# spider_mx8.net
KiCad netlist of a schematic drawn in EAGLE
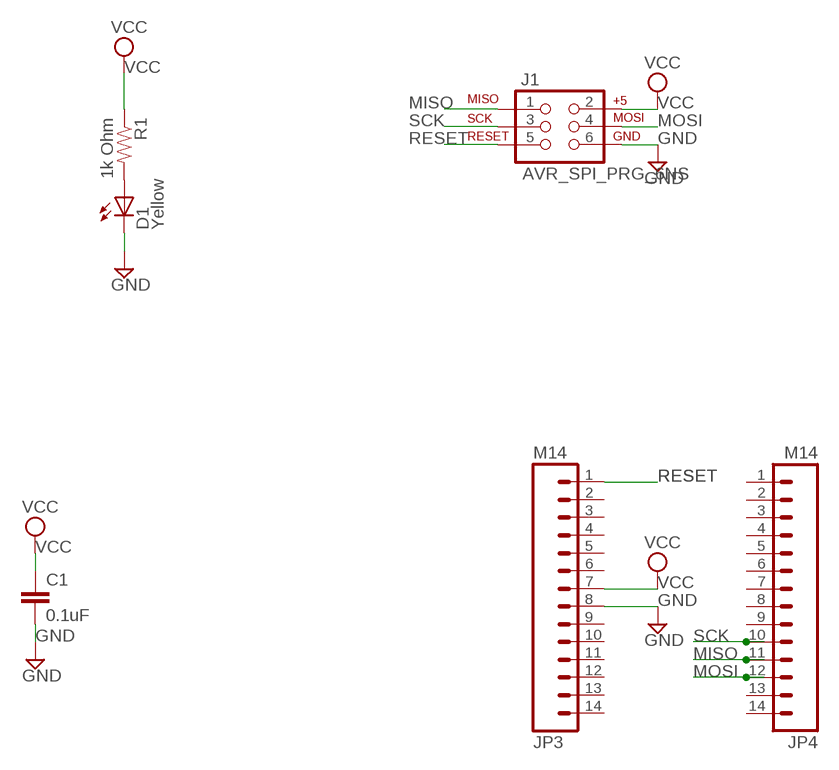
[diagram p0: schematic, sheet 1]

(export (version "E")
  (design (tool "Eeschema 10.0.6"))
  (components
    (comp (ref "C1")
      (value "0.1uF")
      (footprint "eagle-import:1206")
      (libsource (lib "eagle-import") (part "CAP1206"))
    )
    (comp (ref "D1")
      (value "Yellow")
      (footprint "eagle-import:LED-1206")
      (libsource (lib "eagle-import") (part "LED-YELLOWLILYPAD"))
    )
    (comp (ref "J1")
      (value "AVR_SPI_PRG_6NS")
      (footprint "eagle-import:2X3-NS")
      (libsource (lib "eagle-import") (part "AVR_SPI_PRG_6NS"))
    )
    (comp (ref "JP3")
      (value "M14")
      (footprint "eagle-import:1X14")
      (libsource (lib "eagle-import") (part "M14"))
    )
    (comp (ref "JP4")
      (value "M14")
      (footprint "eagle-import:1X14")
      (libsource (lib "eagle-import") (part "M14"))
    )
    (comp (ref "R1")
      (value "1k Ohm")
      (footprint "eagle-import:1206")
      (libsource (lib "eagle-import") (part "RESISTOR1206"))
    )
  )
  (nets
    (net (code "1") (name "/MISO") (class "Default")
      (node (ref "J1") (pin "1") (pinfunction "1_1") (pintype "passive"))
      (node (ref "JP4") (pin "11") (pinfunction "11_11") (pintype "passive"))
    )
    (net (code "2") (name "/MOSI") (class "Default")
      (node (ref "J1") (pin "4") (pinfunction "4_4") (pintype "passive"))
      (node (ref "JP4") (pin "12") (pinfunction "12_12") (pintype "passive"))
    )
    (net (code "3") (name "/RESET") (class "Default")
      (node (ref "J1") (pin "5") (pinfunction "5_5") (pintype "passive"))
      (node (ref "JP3") (pin "1") (pinfunction "1_1") (pintype "passive"))
    )
    (net (code "4") (name "/SCK") (class "Default")
      (node (ref "J1") (pin "3") (pinfunction "3_3") (pintype "passive"))
      (node (ref "JP4") (pin "10") (pinfunction "10_10") (pintype "passive"))
    )
    (net (code "5") (name "GND") (class "Default")
      (node (ref "C1") (pin "2") (pinfunction "2_2") (pintype "passive"))
      (node (ref "D1") (pin "C") (pinfunction "C_C") (pintype "passive"))
      (node (ref "J1") (pin "6") (pinfunction "6_6") (pintype "passive"))
      (node (ref "JP3") (pin "8") (pinfunction "8_8") (pintype "passive"))
    )
    (net (code "6") (name "Net-(D1-PadA)") (class "Default")
      (node (ref "D1") (pin "A") (pinfunction "A_A") (pintype "passive"))
      (node (ref "R1") (pin "2") (pinfunction "2_2") (pintype "passive"))
    )
    (net (code "7") (name "VCC") (class "Default")
      (node (ref "C1") (pin "1") (pinfunction "1_1") (pintype "passive"))
      (node (ref "J1") (pin "2") (pinfunction "2_2") (pintype "passive"))
      (node (ref "JP3") (pin "7") (pinfunction "7_7") (pintype "passive"))
      (node (ref "R1") (pin "1") (pinfunction "1_1") (pintype "passive"))
    )
    (net (code "8") (name "unconnected-(JP3-Pad2)") (class "Default")
      (node (ref "JP3") (pin "2") (pinfunction "2_2") (pintype "passive"))
    )
    (net (code "9") (name "unconnected-(JP3-Pad3)") (class "Default")
      (node (ref "JP3") (pin "3") (pinfunction "3_3") (pintype "passive"))
    )
    (net (code "10") (name "unconnected-(JP3-Pad4)") (class "Default")
      (node (ref "JP3") (pin "4") (pinfunction "4_4") (pintype "passive"))
    )
    (net (code "11") (name "unconnected-(JP3-Pad5)") (class "Default")
      (node (ref "JP3") (pin "5") (pinfunction "5_5") (pintype "passive"))
    )
    (net (code "12") (name "unconnected-(JP3-Pad6)") (class "Default")
      (node (ref "JP3") (pin "6") (pinfunction "6_6") (pintype "passive"))
    )
    (net (code "13") (name "unconnected-(JP3-Pad9)") (class "Default")
      (node (ref "JP3") (pin "9") (pinfunction "9_9") (pintype "passive"))
    )
    (net (code "14") (name "unconnected-(JP3-Pad10)") (class "Default")
      (node (ref "JP3") (pin "10") (pinfunction "10_10") (pintype "passive"))
    )
    (net (code "15") (name "unconnected-(JP3-Pad11)") (class "Default")
      (node (ref "JP3") (pin "11") (pinfunction "11_11") (pintype "passive"))
    )
    (net (code "16") (name "unconnected-(JP3-Pad12)") (class "Default")
      (node (ref "JP3") (pin "12") (pinfunction "12_12") (pintype "passive"))
    )
    (net (code "17") (name "unconnected-(JP3-Pad13)") (class "Default")
      (node (ref "JP3") (pin "13") (pinfunction "13_13") (pintype "passive"))
    )
    (net (code "18") (name "unconnected-(JP3-Pad14)") (class "Default")
      (node (ref "JP3") (pin "14") (pinfunction "14_14") (pintype "passive"))
    )
    (net (code "19") (name "unconnected-(JP4-Pad1)") (class "Default")
      (node (ref "JP4") (pin "1") (pinfunction "1_1") (pintype "passive"))
    )
    (net (code "20") (name "unconnected-(JP4-Pad2)") (class "Default")
      (node (ref "JP4") (pin "2") (pinfunction "2_2") (pintype "passive"))
    )
    (net (code "21") (name "unconnected-(JP4-Pad3)") (class "Default")
      (node (ref "JP4") (pin "3") (pinfunction "3_3") (pintype "passive"))
    )
    (net (code "22") (name "unconnected-(JP4-Pad4)") (class "Default")
      (node (ref "JP4") (pin "4") (pinfunction "4_4") (pintype "passive"))
    )
    (net (code "23") (name "unconnected-(JP4-Pad5)") (class "Default")
      (node (ref "JP4") (pin "5") (pinfunction "5_5") (pintype "passive"))
    )
    (net (code "24") (name "unconnected-(JP4-Pad6)") (class "Default")
      (node (ref "JP4") (pin "6") (pinfunction "6_6") (pintype "passive"))
    )
    (net (code "25") (name "unconnected-(JP4-Pad7)") (class "Default")
      (node (ref "JP4") (pin "7") (pinfunction "7_7") (pintype "passive"))
    )
    (net (code "26") (name "unconnected-(JP4-Pad8)") (class "Default")
      (node (ref "JP4") (pin "8") (pinfunction "8_8") (pintype "passive"))
    )
    (net (code "27") (name "unconnected-(JP4-Pad9)") (class "Default")
      (node (ref "JP4") (pin "9") (pinfunction "9_9") (pintype "passive"))
    )
    (net (code "28") (name "unconnected-(JP4-Pad13)") (class "Default")
      (node (ref "JP4") (pin "13") (pinfunction "13_13") (pintype "passive"))
    )
    (net (code "29") (name "unconnected-(JP4-Pad14)") (class "Default")
      (node (ref "JP4") (pin "14") (pinfunction "14_14") (pintype "passive"))
    )
  )
)
